# GB_Cart_Extender.net
KiCad netlist of a schematic drawn in EAGLE
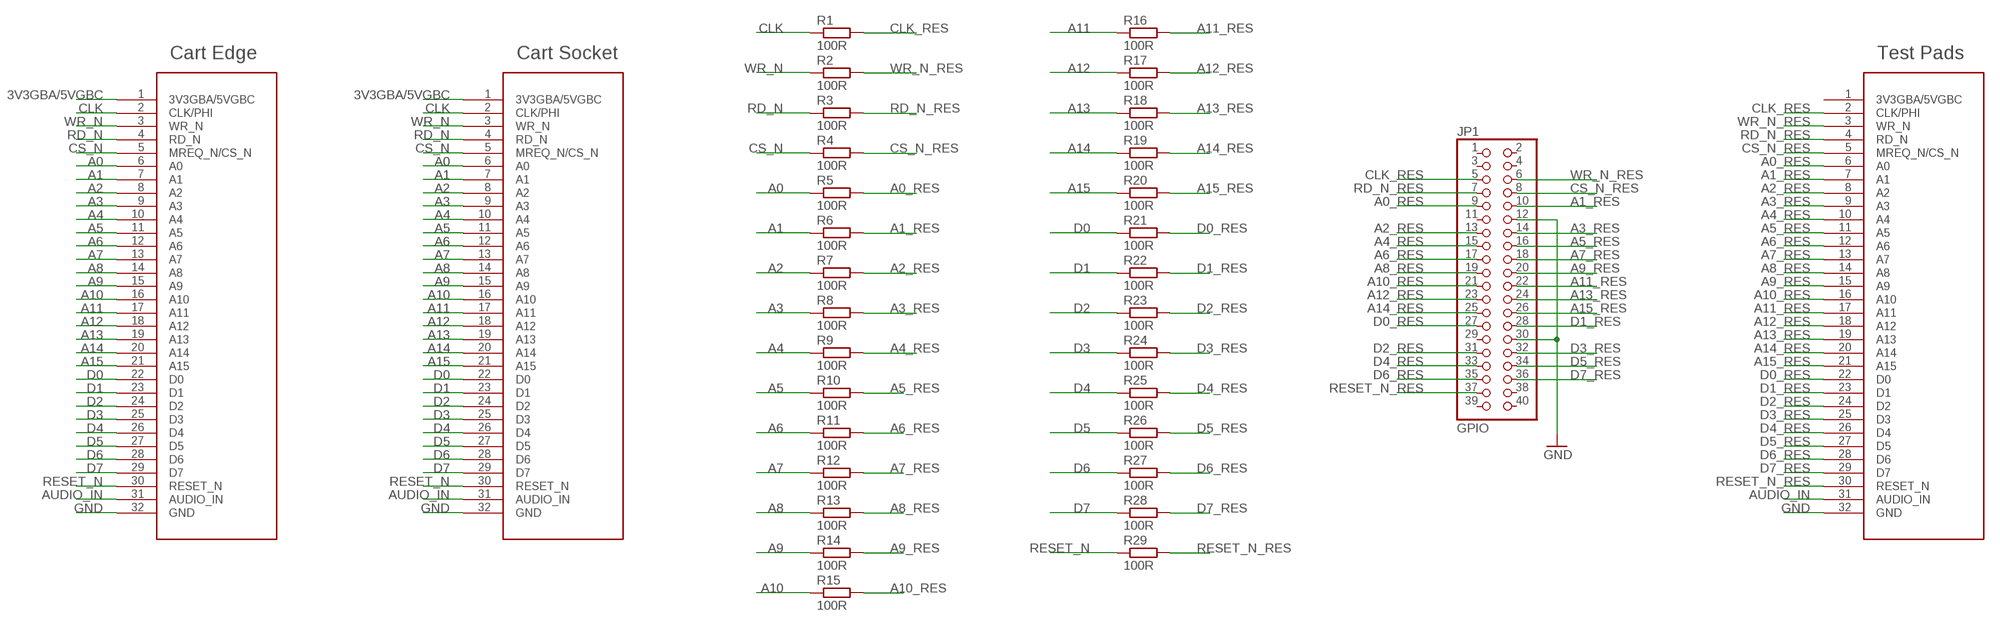
[diagram p0: schematic, sheet 1]

(export (version "E")
  (design (tool "Eeschema 10.0.6"))
  (components
    (comp (ref "EDGE")
      (value "GB_CART_EDGE")
      (footprint "eagle-import:GB_CART_EDGE")
      (libsource (lib "eagle-import") (part "GB_CART_EDGE"))
    )
    (comp (ref "JP1")
      (value "GPIO")
      (footprint "eagle-import:2X20_SMT")
      (fields (field (name "SPICEPREFIX") "X"))
      (libsource (lib "eagle-import") (part "PINHD-2X20SMT"))
    )
    (comp (ref "PADS")
      (value "GB_CART_SOCKET")
      (footprint "eagle-import:GB_CART_1")
      (fields (field (name "SPICEPREFIX") "X"))
      (libsource (lib "eagle-import") (part "GB_CART_SOCKET"))
    )
    (comp (ref "R1")
      (value "100R")
      (footprint "eagle-import:R0603")
      (libsource (lib "eagle-import") (part "R-EU_R0603"))
    )
    (comp (ref "R2")
      (value "100R")
      (footprint "eagle-import:R0603")
      (libsource (lib "eagle-import") (part "R-EU_R0603"))
    )
    (comp (ref "R3")
      (value "100R")
      (footprint "eagle-import:R0603")
      (libsource (lib "eagle-import") (part "R-EU_R0603"))
    )
    (comp (ref "R4")
      (value "100R")
      (footprint "eagle-import:R0603")
      (libsource (lib "eagle-import") (part "R-EU_R0603"))
    )
    (comp (ref "R5")
      (value "100R")
      (footprint "eagle-import:R0603")
      (libsource (lib "eagle-import") (part "R-EU_R0603"))
    )
    (comp (ref "R6")
      (value "100R")
      (footprint "eagle-import:R0603")
      (libsource (lib "eagle-import") (part "R-EU_R0603"))
    )
    (comp (ref "R7")
      (value "100R")
      (footprint "eagle-import:R0603")
      (libsource (lib "eagle-import") (part "R-EU_R0603"))
    )
    (comp (ref "R8")
      (value "100R")
      (footprint "eagle-import:R0603")
      (libsource (lib "eagle-import") (part "R-EU_R0603"))
    )
    (comp (ref "R9")
      (value "100R")
      (footprint "eagle-import:R0603")
      (libsource (lib "eagle-import") (part "R-EU_R0603"))
    )
    (comp (ref "R10")
      (value "100R")
      (footprint "eagle-import:R0603")
      (libsource (lib "eagle-import") (part "R-EU_R0603"))
    )
    (comp (ref "R11")
      (value "100R")
      (footprint "eagle-import:R0603")
      (libsource (lib "eagle-import") (part "R-EU_R0603"))
    )
    (comp (ref "R12")
      (value "100R")
      (footprint "eagle-import:R0603")
      (libsource (lib "eagle-import") (part "R-EU_R0603"))
    )
    (comp (ref "R13")
      (value "100R")
      (footprint "eagle-import:R0603")
      (libsource (lib "eagle-import") (part "R-EU_R0603"))
    )
    (comp (ref "R14")
      (value "100R")
      (footprint "eagle-import:R0603")
      (libsource (lib "eagle-import") (part "R-EU_R0603"))
    )
    (comp (ref "R15")
      (value "100R")
      (footprint "eagle-import:R0603")
      (libsource (lib "eagle-import") (part "R-EU_R0603"))
    )
    (comp (ref "R16")
      (value "100R")
      (footprint "eagle-import:R0603")
      (libsource (lib "eagle-import") (part "R-EU_R0603"))
    )
    (comp (ref "R17")
      (value "100R")
      (footprint "eagle-import:R0603")
      (libsource (lib "eagle-import") (part "R-EU_R0603"))
    )
    (comp (ref "R18")
      (value "100R")
      (footprint "eagle-import:R0603")
      (libsource (lib "eagle-import") (part "R-EU_R0603"))
    )
    (comp (ref "R19")
      (value "100R")
      (footprint "eagle-import:R0603")
      (libsource (lib "eagle-import") (part "R-EU_R0603"))
    )
    (comp (ref "R20")
      (value "100R")
      (footprint "eagle-import:R0603")
      (libsource (lib "eagle-import") (part "R-EU_R0603"))
    )
    (comp (ref "R21")
      (value "100R")
      (footprint "eagle-import:R0603")
      (libsource (lib "eagle-import") (part "R-EU_R0603"))
    )
    (comp (ref "R22")
      (value "100R")
      (footprint "eagle-import:R0603")
      (libsource (lib "eagle-import") (part "R-EU_R0603"))
    )
    (comp (ref "R23")
      (value "100R")
      (footprint "eagle-import:R0603")
      (libsource (lib "eagle-import") (part "R-EU_R0603"))
    )
    (comp (ref "R24")
      (value "100R")
      (footprint "eagle-import:R0603")
      (libsource (lib "eagle-import") (part "R-EU_R0603"))
    )
    (comp (ref "R25")
      (value "100R")
      (footprint "eagle-import:R0603")
      (libsource (lib "eagle-import") (part "R-EU_R0603"))
    )
    (comp (ref "R26")
      (value "100R")
      (footprint "eagle-import:R0603")
      (libsource (lib "eagle-import") (part "R-EU_R0603"))
    )
    (comp (ref "R27")
      (value "100R")
      (footprint "eagle-import:R0603")
      (libsource (lib "eagle-import") (part "R-EU_R0603"))
    )
    (comp (ref "R28")
      (value "100R")
      (footprint "eagle-import:R0603")
      (libsource (lib "eagle-import") (part "R-EU_R0603"))
    )
    (comp (ref "R29")
      (value "100R")
      (footprint "eagle-import:R0603")
      (libsource (lib "eagle-import") (part "R-EU_R0603"))
    )
    (comp (ref "SOCKET")
      (value "GB_CART_SOCKET")
      (footprint "eagle-import:GB_CART_1")
      (libsource (lib "eagle-import") (part "GB_CART_SOCKET"))
    )
  )
  (nets
    (net (code "1") (name "/3V3GBA{slash}5VGBC") (class "Default")
      (node (ref "EDGE") (pin "1") (pinfunction "3V3GBA/5VGBC_1") (pintype "bidirectional"))
      (node (ref "SOCKET") (pin "1") (pinfunction "3V3GBA/5VGBC_1") (pintype "bidirectional"))
    )
    (net (code "2") (name "/A0") (class "Default")
      (node (ref "EDGE") (pin "6") (pinfunction "A0_6") (pintype "bidirectional"))
      (node (ref "R5") (pin "1") (pinfunction "1_1") (pintype "passive"))
      (node (ref "SOCKET") (pin "6") (pinfunction "A0_6") (pintype "bidirectional"))
    )
    (net (code "3") (name "/A0_RES") (class "Default")
      (node (ref "JP1") (pin "9") (pinfunction "9_9") (pintype "passive"))
      (node (ref "PADS") (pin "6") (pinfunction "A0_6") (pintype "bidirectional"))
      (node (ref "R5") (pin "2") (pinfunction "2_2") (pintype "passive"))
    )
    (net (code "4") (name "/A1") (class "Default")
      (node (ref "EDGE") (pin "7") (pinfunction "A1_7") (pintype "bidirectional"))
      (node (ref "R6") (pin "1") (pinfunction "1_1") (pintype "passive"))
      (node (ref "SOCKET") (pin "7") (pinfunction "A1_7") (pintype "bidirectional"))
    )
    (net (code "5") (name "/A1_RES") (class "Default")
      (node (ref "JP1") (pin "10") (pinfunction "10_10") (pintype "passive"))
      (node (ref "PADS") (pin "7") (pinfunction "A1_7") (pintype "bidirectional"))
      (node (ref "R6") (pin "2") (pinfunction "2_2") (pintype "passive"))
    )
    (net (code "6") (name "/A2") (class "Default")
      (node (ref "EDGE") (pin "8") (pinfunction "A2_8") (pintype "bidirectional"))
      (node (ref "R7") (pin "1") (pinfunction "1_1") (pintype "passive"))
      (node (ref "SOCKET") (pin "8") (pinfunction "A2_8") (pintype "bidirectional"))
    )
    (net (code "7") (name "/A2_RES") (class "Default")
      (node (ref "JP1") (pin "13") (pinfunction "13_13") (pintype "passive"))
      (node (ref "PADS") (pin "8") (pinfunction "A2_8") (pintype "bidirectional"))
      (node (ref "R7") (pin "2") (pinfunction "2_2") (pintype "passive"))
    )
    (net (code "8") (name "/A3") (class "Default")
      (node (ref "EDGE") (pin "9") (pinfunction "A3_9") (pintype "bidirectional"))
      (node (ref "R8") (pin "1") (pinfunction "1_1") (pintype "passive"))
      (node (ref "SOCKET") (pin "9") (pinfunction "A3_9") (pintype "bidirectional"))
    )
    (net (code "9") (name "/A3_RES") (class "Default")
      (node (ref "JP1") (pin "14") (pinfunction "14_14") (pintype "passive"))
      (node (ref "PADS") (pin "9") (pinfunction "A3_9") (pintype "bidirectional"))
      (node (ref "R8") (pin "2") (pinfunction "2_2") (pintype "passive"))
    )
    (net (code "10") (name "/A4") (class "Default")
      (node (ref "EDGE") (pin "10") (pinfunction "A4_10") (pintype "bidirectional"))
      (node (ref "R9") (pin "1") (pinfunction "1_1") (pintype "passive"))
      (node (ref "SOCKET") (pin "10") (pinfunction "A4_10") (pintype "bidirectional"))
    )
    (net (code "11") (name "/A4_RES") (class "Default")
      (node (ref "JP1") (pin "15") (pinfunction "15_15") (pintype "passive"))
      (node (ref "PADS") (pin "10") (pinfunction "A4_10") (pintype "bidirectional"))
      (node (ref "R9") (pin "2") (pinfunction "2_2") (pintype "passive"))
    )
    (net (code "12") (name "/A5") (class "Default")
      (node (ref "EDGE") (pin "11") (pinfunction "A5_11") (pintype "bidirectional"))
      (node (ref "R10") (pin "1") (pinfunction "1_1") (pintype "passive"))
      (node (ref "SOCKET") (pin "11") (pinfunction "A5_11") (pintype "bidirectional"))
    )
    (net (code "13") (name "/A5_RES") (class "Default")
      (node (ref "JP1") (pin "16") (pinfunction "16_16") (pintype "passive"))
      (node (ref "PADS") (pin "11") (pinfunction "A5_11") (pintype "bidirectional"))
      (node (ref "R10") (pin "2") (pinfunction "2_2") (pintype "passive"))
    )
    (net (code "14") (name "/A6") (class "Default")
      (node (ref "EDGE") (pin "12") (pinfunction "A6_12") (pintype "bidirectional"))
      (node (ref "R11") (pin "1") (pinfunction "1_1") (pintype "passive"))
      (node (ref "SOCKET") (pin "12") (pinfunction "A6_12") (pintype "bidirectional"))
    )
    (net (code "15") (name "/A6_RES") (class "Default")
      (node (ref "JP1") (pin "17") (pinfunction "17_17") (pintype "passive"))
      (node (ref "PADS") (pin "12") (pinfunction "A6_12") (pintype "bidirectional"))
      (node (ref "R11") (pin "2") (pinfunction "2_2") (pintype "passive"))
    )
    (net (code "16") (name "/A7") (class "Default")
      (node (ref "EDGE") (pin "13") (pinfunction "A7_13") (pintype "bidirectional"))
      (node (ref "R12") (pin "1") (pinfunction "1_1") (pintype "passive"))
      (node (ref "SOCKET") (pin "13") (pinfunction "A7_13") (pintype "bidirectional"))
    )
    (net (code "17") (name "/A7_RES") (class "Default")
      (node (ref "JP1") (pin "18") (pinfunction "18_18") (pintype "passive"))
      (node (ref "PADS") (pin "13") (pinfunction "A7_13") (pintype "bidirectional"))
      (node (ref "R12") (pin "2") (pinfunction "2_2") (pintype "passive"))
    )
    (net (code "18") (name "/A8") (class "Default")
      (node (ref "EDGE") (pin "14") (pinfunction "A8_14") (pintype "bidirectional"))
      (node (ref "R13") (pin "1") (pinfunction "1_1") (pintype "passive"))
      (node (ref "SOCKET") (pin "14") (pinfunction "A8_14") (pintype "bidirectional"))
    )
    (net (code "19") (name "/A8_RES") (class "Default")
      (node (ref "JP1") (pin "19") (pinfunction "19_19") (pintype "passive"))
      (node (ref "PADS") (pin "14") (pinfunction "A8_14") (pintype "bidirectional"))
      (node (ref "R13") (pin "2") (pinfunction "2_2") (pintype "passive"))
    )
    (net (code "20") (name "/A9") (class "Default")
      (node (ref "EDGE") (pin "15") (pinfunction "A9_15") (pintype "bidirectional"))
      (node (ref "R14") (pin "1") (pinfunction "1_1") (pintype "passive"))
      (node (ref "SOCKET") (pin "15") (pinfunction "A9_15") (pintype "bidirectional"))
    )
    (net (code "21") (name "/A9_RES") (class "Default")
      (node (ref "JP1") (pin "20") (pinfunction "20_20") (pintype "passive"))
      (node (ref "PADS") (pin "15") (pinfunction "A9_15") (pintype "bidirectional"))
      (node (ref "R14") (pin "2") (pinfunction "2_2") (pintype "passive"))
    )
    (net (code "22") (name "/A10") (class "Default")
      (node (ref "EDGE") (pin "16") (pinfunction "A10_16") (pintype "bidirectional"))
      (node (ref "R15") (pin "1") (pinfunction "1_1") (pintype "passive"))
      (node (ref "SOCKET") (pin "16") (pinfunction "A10_16") (pintype "bidirectional"))
    )
    (net (code "23") (name "/A10_RES") (class "Default")
      (node (ref "JP1") (pin "21") (pinfunction "21_21") (pintype "passive"))
      (node (ref "PADS") (pin "16") (pinfunction "A10_16") (pintype "bidirectional"))
      (node (ref "R15") (pin "2") (pinfunction "2_2") (pintype "passive"))
    )
    (net (code "24") (name "/A11") (class "Default")
      (node (ref "EDGE") (pin "17") (pinfunction "A11_17") (pintype "bidirectional"))
      (node (ref "R16") (pin "1") (pinfunction "1_1") (pintype "passive"))
      (node (ref "SOCKET") (pin "17") (pinfunction "A11_17") (pintype "bidirectional"))
    )
    (net (code "25") (name "/A11_RES") (class "Default")
      (node (ref "JP1") (pin "22") (pinfunction "22_22") (pintype "passive"))
      (node (ref "PADS") (pin "17") (pinfunction "A11_17") (pintype "bidirectional"))
      (node (ref "R16") (pin "2") (pinfunction "2_2") (pintype "passive"))
    )
    (net (code "26") (name "/A12") (class "Default")
      (node (ref "EDGE") (pin "18") (pinfunction "A12_18") (pintype "bidirectional"))
      (node (ref "R17") (pin "1") (pinfunction "1_1") (pintype "passive"))
      (node (ref "SOCKET") (pin "18") (pinfunction "A12_18") (pintype "bidirectional"))
    )
    (net (code "27") (name "/A12_RES") (class "Default")
      (node (ref "JP1") (pin "23") (pinfunction "23_23") (pintype "passive"))
      (node (ref "PADS") (pin "18") (pinfunction "A12_18") (pintype "bidirectional"))
      (node (ref "R17") (pin "2") (pinfunction "2_2") (pintype "passive"))
    )
    (net (code "28") (name "/A13") (class "Default")
      (node (ref "EDGE") (pin "19") (pinfunction "A13_19") (pintype "bidirectional"))
      (node (ref "R18") (pin "1") (pinfunction "1_1") (pintype "passive"))
      (node (ref "SOCKET") (pin "19") (pinfunction "A13_19") (pintype "bidirectional"))
    )
    (net (code "29") (name "/A13_RES") (class "Default")
      (node (ref "JP1") (pin "24") (pinfunction "24_24") (pintype "passive"))
      (node (ref "PADS") (pin "19") (pinfunction "A13_19") (pintype "bidirectional"))
      (node (ref "R18") (pin "2") (pinfunction "2_2") (pintype "passive"))
    )
    (net (code "30") (name "/A14") (class "Default")
      (node (ref "EDGE") (pin "20") (pinfunction "A14_20") (pintype "bidirectional"))
      (node (ref "R19") (pin "1") (pinfunction "1_1") (pintype "passive"))
      (node (ref "SOCKET") (pin "20") (pinfunction "A14_20") (pintype "bidirectional"))
    )
    (net (code "31") (name "/A14_RES") (class "Default")
      (node (ref "JP1") (pin "25") (pinfunction "25_25") (pintype "passive"))
      (node (ref "PADS") (pin "20") (pinfunction "A14_20") (pintype "bidirectional"))
      (node (ref "R19") (pin "2") (pinfunction "2_2") (pintype "passive"))
    )
    (net (code "32") (name "/A15") (class "Default")
      (node (ref "EDGE") (pin "21") (pinfunction "A15_21") (pintype "bidirectional"))
      (node (ref "R20") (pin "1") (pinfunction "1_1") (pintype "passive"))
      (node (ref "SOCKET") (pin "21") (pinfunction "A15_21") (pintype "bidirectional"))
    )
    (net (code "33") (name "/A15_RES") (class "Default")
      (node (ref "JP1") (pin "26") (pinfunction "26_26") (pintype "passive"))
      (node (ref "PADS") (pin "21") (pinfunction "A15_21") (pintype "bidirectional"))
      (node (ref "R20") (pin "2") (pinfunction "2_2") (pintype "passive"))
    )
    (net (code "34") (name "/AUDIO_IN") (class "Default")
      (node (ref "EDGE") (pin "31") (pinfunction "AUDIO_IN_31") (pintype "bidirectional"))
      (node (ref "PADS") (pin "31") (pinfunction "AUDIO_IN_31") (pintype "bidirectional"))
      (node (ref "SOCKET") (pin "31") (pinfunction "AUDIO_IN_31") (pintype "bidirectional"))
    )
    (net (code "35") (name "/CLK") (class "Default")
      (node (ref "EDGE") (pin "2") (pinfunction "CLK/PHI_2") (pintype "bidirectional"))
      (node (ref "R1") (pin "1") (pinfunction "1_1") (pintype "passive"))
      (node (ref "SOCKET") (pin "2") (pinfunction "CLK/PHI_2") (pintype "bidirectional"))
    )
    (net (code "36") (name "/CLK_RES") (class "Default")
      (node (ref "JP1") (pin "5") (pinfunction "5_5") (pintype "passive"))
      (node (ref "PADS") (pin "2") (pinfunction "CLK/PHI_2") (pintype "bidirectional"))
      (node (ref "R1") (pin "2") (pinfunction "2_2") (pintype "passive"))
    )
    (net (code "37") (name "/CS_N") (class "Default")
      (node (ref "EDGE") (pin "5") (pinfunction "MREQ_N/CS_N_5") (pintype "bidirectional"))
      (node (ref "R4") (pin "1") (pinfunction "1_1") (pintype "passive"))
      (node (ref "SOCKET") (pin "5") (pinfunction "MREQ_N/CS_N_5") (pintype "bidirectional"))
    )
    (net (code "38") (name "/CS_N_RES") (class "Default")
      (node (ref "JP1") (pin "8") (pinfunction "8_8") (pintype "passive"))
      (node (ref "PADS") (pin "5") (pinfunction "MREQ_N/CS_N_5") (pintype "bidirectional"))
      (node (ref "R4") (pin "2") (pinfunction "2_2") (pintype "passive"))
    )
    (net (code "39") (name "/D0") (class "Default")
      (node (ref "EDGE") (pin "22") (pinfunction "D0_22") (pintype "bidirectional"))
      (node (ref "R21") (pin "1") (pinfunction "1_1") (pintype "passive"))
      (node (ref "SOCKET") (pin "22") (pinfunction "D0_22") (pintype "bidirectional"))
    )
    (net (code "40") (name "/D0_RES") (class "Default")
      (node (ref "JP1") (pin "27") (pinfunction "27_27") (pintype "passive"))
      (node (ref "PADS") (pin "22") (pinfunction "D0_22") (pintype "bidirectional"))
      (node (ref "R21") (pin "2") (pinfunction "2_2") (pintype "passive"))
    )
    (net (code "41") (name "/D1") (class "Default")
      (node (ref "EDGE") (pin "23") (pinfunction "D1_23") (pintype "bidirectional"))
      (node (ref "R22") (pin "1") (pinfunction "1_1") (pintype "passive"))
      (node (ref "SOCKET") (pin "23") (pinfunction "D1_23") (pintype "bidirectional"))
    )
    (net (code "42") (name "/D1_RES") (class "Default")
      (node (ref "JP1") (pin "28") (pinfunction "28_28") (pintype "passive"))
      (node (ref "PADS") (pin "23") (pinfunction "D1_23") (pintype "bidirectional"))
      (node (ref "R22") (pin "2") (pinfunction "2_2") (pintype "passive"))
    )
    (net (code "43") (name "/D2") (class "Default")
      (node (ref "EDGE") (pin "24") (pinfunction "D2_24") (pintype "bidirectional"))
      (node (ref "R23") (pin "1") (pinfunction "1_1") (pintype "passive"))
      (node (ref "SOCKET") (pin "24") (pinfunction "D2_24") (pintype "bidirectional"))
    )
    (net (code "44") (name "/D2_RES") (class "Default")
      (node (ref "JP1") (pin "31") (pinfunction "31_31") (pintype "passive"))
      (node (ref "PADS") (pin "24") (pinfunction "D2_24") (pintype "bidirectional"))
      (node (ref "R23") (pin "2") (pinfunction "2_2") (pintype "passive"))
    )
    (net (code "45") (name "/D3") (class "Default")
      (node (ref "EDGE") (pin "25") (pinfunction "D3_25") (pintype "bidirectional"))
      (node (ref "R24") (pin "1") (pinfunction "1_1") (pintype "passive"))
      (node (ref "SOCKET") (pin "25") (pinfunction "D3_25") (pintype "bidirectional"))
    )
    (net (code "46") (name "/D3_RES") (class "Default")
      (node (ref "JP1") (pin "32") (pinfunction "32_32") (pintype "passive"))
      (node (ref "PADS") (pin "25") (pinfunction "D3_25") (pintype "bidirectional"))
      (node (ref "R24") (pin "2") (pinfunction "2_2") (pintype "passive"))
    )
    (net (code "47") (name "/D4") (class "Default")
      (node (ref "EDGE") (pin "26") (pinfunction "D4_26") (pintype "bidirectional"))
      (node (ref "R25") (pin "1") (pinfunction "1_1") (pintype "passive"))
      (node (ref "SOCKET") (pin "26") (pinfunction "D4_26") (pintype "bidirectional"))
    )
    (net (code "48") (name "/D4_RES") (class "Default")
      (node (ref "JP1") (pin "33") (pinfunction "33_33") (pintype "passive"))
      (node (ref "PADS") (pin "26") (pinfunction "D4_26") (pintype "bidirectional"))
      (node (ref "R25") (pin "2") (pinfunction "2_2") (pintype "passive"))
    )
    (net (code "49") (name "/D5") (class "Default")
      (node (ref "EDGE") (pin "27") (pinfunction "D5_27") (pintype "bidirectional"))
      (node (ref "R26") (pin "1") (pinfunction "1_1") (pintype "passive"))
      (node (ref "SOCKET") (pin "27") (pinfunction "D5_27") (pintype "bidirectional"))
    )
    (net (code "50") (name "/D5_RES") (class "Default")
      (node (ref "JP1") (pin "34") (pinfunction "34_34") (pintype "passive"))
      (node (ref "PADS") (pin "27") (pinfunction "D5_27") (pintype "bidirectional"))
      (node (ref "R26") (pin "2") (pinfunction "2_2") (pintype "passive"))
    )
    (net (code "51") (name "/D6") (class "Default")
      (node (ref "EDGE") (pin "28") (pinfunction "D6_28") (pintype "bidirectional"))
      (node (ref "R27") (pin "1") (pinfunction "1_1") (pintype "passive"))
      (node (ref "SOCKET") (pin "28") (pinfunction "D6_28") (pintype "bidirectional"))
    )
    (net (code "52") (name "/D6_RES") (class "Default")
      (node (ref "JP1") (pin "35") (pinfunction "35_35") (pintype "passive"))
      (node (ref "PADS") (pin "28") (pinfunction "D6_28") (pintype "bidirectional"))
      (node (ref "R27") (pin "2") (pinfunction "2_2") (pintype "passive"))
    )
    (net (code "53") (name "/D7") (class "Default")
      (node (ref "EDGE") (pin "29") (pinfunction "D7_29") (pintype "bidirectional"))
      (node (ref "R28") (pin "1") (pinfunction "1_1") (pintype "passive"))
      (node (ref "SOCKET") (pin "29") (pinfunction "D7_29") (pintype "bidirectional"))
    )
    (net (code "54") (name "/D7_RES") (class "Default")
      (node (ref "JP1") (pin "36") (pinfunction "36_36") (pintype "passive"))
      (node (ref "PADS") (pin "29") (pinfunction "D7_29") (pintype "bidirectional"))
      (node (ref "R28") (pin "2") (pinfunction "2_2") (pintype "passive"))
    )
    (net (code "55") (name "/RD_N") (class "Default")
      (node (ref "EDGE") (pin "4") (pinfunction "RD_N_4") (pintype "bidirectional"))
      (node (ref "R3") (pin "1") (pinfunction "1_1") (pintype "passive"))
      (node (ref "SOCKET") (pin "4") (pinfunction "RD_N_4") (pintype "bidirectional"))
    )
    (net (code "56") (name "/RD_N_RES") (class "Default")
      (node (ref "JP1") (pin "7") (pinfunction "7_7") (pintype "passive"))
      (node (ref "PADS") (pin "4") (pinfunction "RD_N_4") (pintype "bidirectional"))
      (node (ref "R3") (pin "2") (pinfunction "2_2") (pintype "passive"))
    )
    (net (code "57") (name "/RESET_N") (class "Default")
      (node (ref "EDGE") (pin "30") (pinfunction "RESET_N_30") (pintype "bidirectional"))
      (node (ref "R29") (pin "1") (pinfunction "1_1") (pintype "passive"))
      (node (ref "SOCKET") (pin "30") (pinfunction "RESET_N_30") (pintype "bidirectional"))
    )
    (net (code "58") (name "/RESET_N_RES") (class "Default")
      (node (ref "JP1") (pin "37") (pinfunction "37_37") (pintype "passive"))
      (node (ref "PADS") (pin "30") (pinfunction "RESET_N_30") (pintype "bidirectional"))
      (node (ref "R29") (pin "2") (pinfunction "2_2") (pintype "passive"))
    )
    (net (code "59") (name "/WR_N") (class "Default")
      (node (ref "EDGE") (pin "3") (pinfunction "WR_N_3") (pintype "bidirectional"))
      (node (ref "R2") (pin "1") (pinfunction "1_1") (pintype "passive"))
      (node (ref "SOCKET") (pin "3") (pinfunction "WR_N_3") (pintype "bidirectional"))
    )
    (net (code "60") (name "/WR_N_RES") (class "Default")
      (node (ref "JP1") (pin "6") (pinfunction "6_6") (pintype "passive"))
      (node (ref "PADS") (pin "3") (pinfunction "WR_N_3") (pintype "bidirectional"))
      (node (ref "R2") (pin "2") (pinfunction "2_2") (pintype "passive"))
    )
    (net (code "61") (name "GND") (class "Default")
      (node (ref "EDGE") (pin "32") (pinfunction "GND_32") (pintype "bidirectional"))
      (node (ref "JP1") (pin "12") (pinfunction "12_12") (pintype "passive"))
      (node (ref "JP1") (pin "30") (pinfunction "30_30") (pintype "passive"))
      (node (ref "PADS") (pin "32") (pinfunction "GND_32") (pintype "bidirectional"))
      (node (ref "SOCKET") (pin "32") (pinfunction "GND_32") (pintype "bidirectional"))
    )
    (net (code "62") (name "unconnected-(JP1-Pad1)") (class "Default")
      (node (ref "JP1") (pin "1") (pinfunction "1_1") (pintype "passive"))
    )
    (net (code "63") (name "unconnected-(JP1-Pad2)") (class "Default")
      (node (ref "JP1") (pin "2") (pinfunction "2_2") (pintype "passive"))
    )
    (net (code "64") (name "unconnected-(JP1-Pad3)") (class "Default")
      (node (ref "JP1") (pin "3") (pinfunction "3_3") (pintype "passive"))
    )
    (net (code "65") (name "unconnected-(JP1-Pad4)") (class "Default")
      (node (ref "JP1") (pin "4") (pinfunction "4_4") (pintype "passive"))
    )
    (net (code "66") (name "unconnected-(JP1-Pad11)") (class "Default")
      (node (ref "JP1") (pin "11") (pinfunction "11_11") (pintype "passive"))
    )
    (net (code "67") (name "unconnected-(JP1-Pad29)") (class "Default")
      (node (ref "JP1") (pin "29") (pinfunction "29_29") (pintype "passive"))
    )
    (net (code "68") (name "unconnected-(JP1-Pad38)") (class "Default")
      (node (ref "JP1") (pin "38") (pinfunction "38_38") (pintype "passive"))
    )
    (net (code "69") (name "unconnected-(JP1-Pad39)") (class "Default")
      (node (ref "JP1") (pin "39") (pinfunction "39_39") (pintype "passive"))
    )
    (net (code "70") (name "unconnected-(JP1-Pad40)") (class "Default")
      (node (ref "JP1") (pin "40") (pinfunction "40_40") (pintype "passive"))
    )
    (net (code "71") (name "unconnected-(PADS-3V3GBA{slash}5VGBC-Pad1)") (class "Default")
      (node (ref "PADS") (pin "1") (pinfunction "3V3GBA/5VGBC_1") (pintype "bidirectional"))
    )
  )
)
